# Adafruit_PAM8302.net
KiCad netlist of a schematic drawn in EAGLE
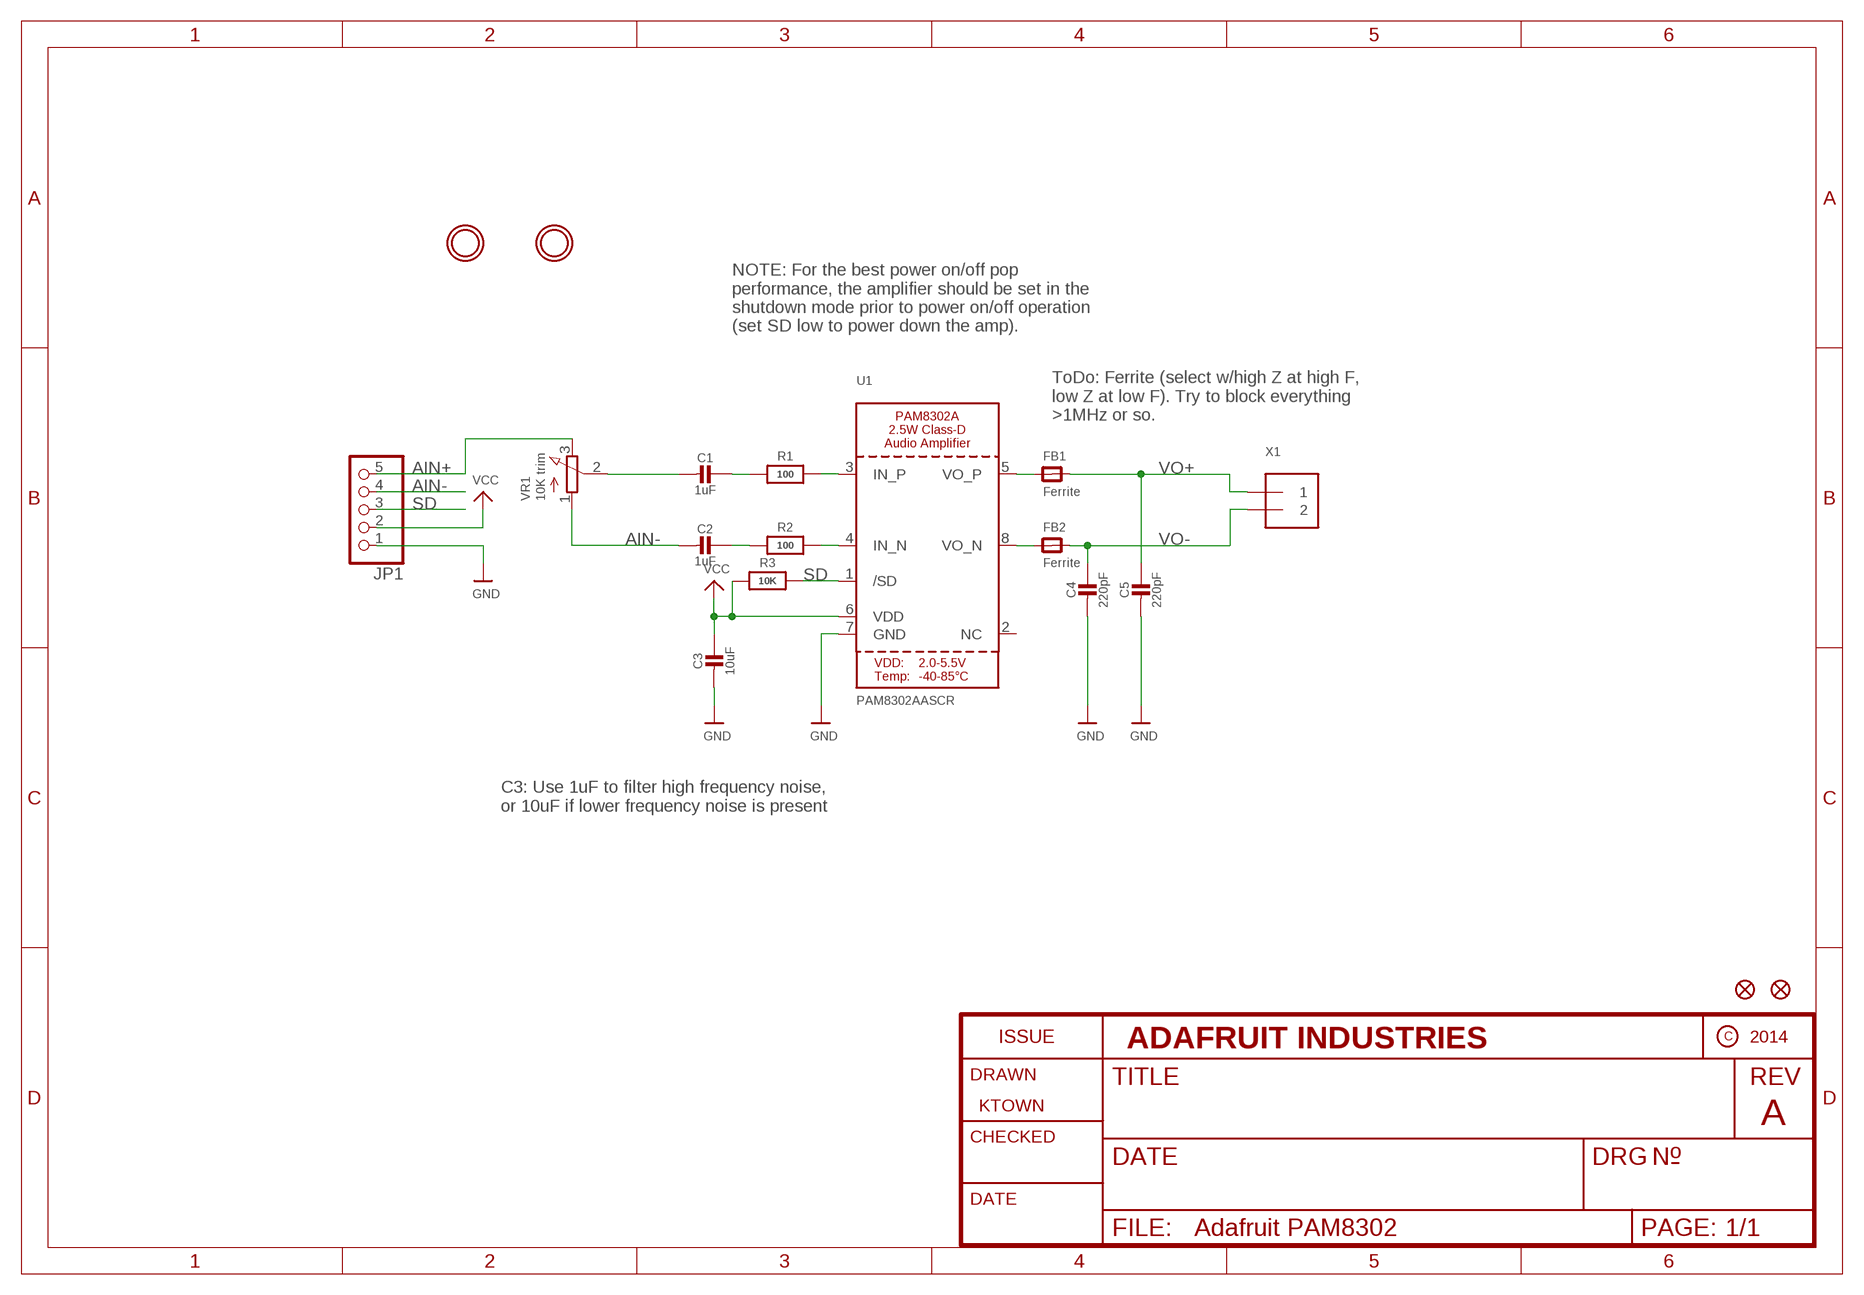
[diagram p0: schematic, sheet 1]

(export (version "E")
  (design (tool "Eeschema 10.0.6"))
  (components
    (comp (ref "C1")
      (value "1uF")
      (footprint "eagle-import:0805-NO")
      (libsource (lib "eagle-import") (part "CAP_CERAMIC0805-NOOUTLINE"))
    )
    (comp (ref "C2")
      (value "1uF")
      (footprint "eagle-import:0805-NO")
      (libsource (lib "eagle-import") (part "CAP_CERAMIC0805-NOOUTLINE"))
    )
    (comp (ref "C3")
      (value "10uF")
      (footprint "eagle-import:0805-NO")
      (libsource (lib "eagle-import") (part "CAP_CERAMIC0805-NOOUTLINE"))
    )
    (comp (ref "C4")
      (value "220pF")
      (footprint "eagle-import:0805-NO")
      (libsource (lib "eagle-import") (part "CAP_CERAMIC0805-NOOUTLINE"))
    )
    (comp (ref "C5")
      (value "220pF")
      (footprint "eagle-import:0805-NO")
      (libsource (lib "eagle-import") (part "CAP_CERAMIC0805-NOOUTLINE"))
    )
    (comp (ref "FB1")
      (value "Ferrite")
      (footprint "eagle-import:_0805")
      (libsource (lib "eagle-import") (part "FERRITE_0805"))
    )
    (comp (ref "FB2")
      (value "Ferrite")
      (footprint "eagle-import:_0805")
      (libsource (lib "eagle-import") (part "FERRITE_0805"))
    )
    (comp (ref "FID1")
      (value "FIDUCIAL\"\"")
      (footprint "eagle-import:FIDUCIAL_1MM")
      (libsource (lib "eagle-import") (part "FIDUCIAL{dblquote}{dblquote}"))
    )
    (comp (ref "FID2")
      (value "FIDUCIAL\"\"")
      (footprint "eagle-import:FIDUCIAL_1MM")
      (libsource (lib "eagle-import") (part "FIDUCIAL{dblquote}{dblquote}"))
    )
    (comp (ref "JP1")
      (value "HEADER-1X570MIL")
      (footprint "eagle-import:1X05_ROUND_70")
      (libsource (lib "eagle-import") (part "HEADER-1X570MIL"))
    )
    (comp (ref "R1")
      (value "100")
      (footprint "eagle-import:0805-NO")
      (libsource (lib "eagle-import") (part "RESISTOR0805_NOOUTLINE"))
    )
    (comp (ref "R2")
      (value "100")
      (footprint "eagle-import:0805-NO")
      (libsource (lib "eagle-import") (part "RESISTOR0805_NOOUTLINE"))
    )
    (comp (ref "R3")
      (value "10K")
      (footprint "eagle-import:0805-NO")
      (libsource (lib "eagle-import") (part "RESISTOR0805_NOOUTLINE"))
    )
    (comp (ref "U$10")
      (value "MOUNTINGHOLE2.0")
      (footprint "eagle-import:MOUNTINGHOLE_2.0_PLATED")
      (libsource (lib "eagle-import") (part "MOUNTINGHOLE2.0"))
    )
    (comp (ref "U$11")
      (value "MOUNTINGHOLE2.0")
      (footprint "eagle-import:MOUNTINGHOLE_2.0_PLATED")
      (libsource (lib "eagle-import") (part "MOUNTINGHOLE2.0"))
    )
    (comp (ref "U1")
      (value "PAM8302AASCR")
      (footprint "eagle-import:MSOP8_0.65MM")
      (libsource (lib "eagle-import") (part "AUDIOAMP_PAM8302A"))
    )
    (comp (ref "VR1")
      (value "10K trim")
      (footprint "eagle-import:TRIMPOT_BOURNS_3303W")
      (libsource (lib "eagle-import") (part "TRIMPOT3303W/X"))
    )
    (comp (ref "X1")
      (value "TERMBLOCK_1X2")
      (footprint "eagle-import:TERMBLOCK_1X2-3.5MM")
      (libsource (lib "eagle-import") (part "TERMBLOCK_1X2"))
    )
  )
  (nets
    (net (code "1") (name "/AIN+") (class "Default")
      (node (ref "JP1") (pin "5") (pinfunction "5_5") (pintype "passive"))
      (node (ref "VR1") (pin "3") (pinfunction "E_3") (pintype "passive"))
    )
    (net (code "2") (name "/AIN-") (class "Default")
      (node (ref "C2") (pin "2") (pinfunction "2_2") (pintype "passive"))
      (node (ref "JP1") (pin "4") (pinfunction "4_4") (pintype "passive"))
      (node (ref "VR1") (pin "1") (pinfunction "A_1") (pintype "passive"))
    )
    (net (code "3") (name "/SD") (class "Default")
      (node (ref "JP1") (pin "3") (pinfunction "3_3") (pintype "passive"))
      (node (ref "R3") (pin "2") (pinfunction "2_2") (pintype "passive"))
      (node (ref "U1") (pin "1") (pinfunction "/SD_1") (pintype "input"))
    )
    (net (code "4") (name "/VO+") (class "Default")
      (node (ref "C5") (pin "1") (pinfunction "1_1") (pintype "passive"))
      (node (ref "FB1") (pin "2") (pinfunction "P$2_2") (pintype "passive"))
      (node (ref "X1") (pin "1") (pinfunction "1_1") (pintype "passive"))
    )
    (net (code "5") (name "/VO-") (class "Default")
      (node (ref "C4") (pin "1") (pinfunction "1_1") (pintype "passive"))
      (node (ref "FB2") (pin "2") (pinfunction "P$2_2") (pintype "passive"))
      (node (ref "X1") (pin "2") (pinfunction "2_2") (pintype "passive"))
    )
    (net (code "6") (name "GND") (class "Default")
      (node (ref "C3") (pin "2") (pinfunction "2_2") (pintype "passive"))
      (node (ref "C4") (pin "2") (pinfunction "2_2") (pintype "passive"))
      (node (ref "C5") (pin "2") (pinfunction "2_2") (pintype "passive"))
      (node (ref "JP1") (pin "1") (pinfunction "1_1") (pintype "passive"))
      (node (ref "U1") (pin "7") (pinfunction "GND_7") (pintype "power_in"))
    )
    (net (code "7") (name "Net-(C1-Pad1)") (class "Default")
      (node (ref "C1") (pin "1") (pinfunction "1_1") (pintype "passive"))
      (node (ref "R1") (pin "1") (pinfunction "1_1") (pintype "passive"))
    )
    (net (code "8") (name "Net-(C2-Pad1)") (class "Default")
      (node (ref "C2") (pin "1") (pinfunction "1_1") (pintype "passive"))
      (node (ref "R2") (pin "1") (pinfunction "1_1") (pintype "passive"))
    )
    (net (code "9") (name "Net-(FB1-P$1)") (class "Default")
      (node (ref "FB1") (pin "1") (pinfunction "P$1_1") (pintype "passive"))
      (node (ref "U1") (pin "5") (pinfunction "VO_P_5") (pintype "output"))
    )
    (net (code "10") (name "Net-(FB2-P$1)") (class "Default")
      (node (ref "FB2") (pin "1") (pinfunction "P$1_1") (pintype "passive"))
      (node (ref "U1") (pin "8") (pinfunction "VO_N_8") (pintype "output"))
    )
    (net (code "11") (name "Net-(U1-IN_N)") (class "Default")
      (node (ref "R2") (pin "2") (pinfunction "2_2") (pintype "passive"))
      (node (ref "U1") (pin "4") (pinfunction "IN_N_4") (pintype "input"))
    )
    (net (code "12") (name "Net-(U1-IN_P)") (class "Default")
      (node (ref "R1") (pin "2") (pinfunction "2_2") (pintype "passive"))
      (node (ref "U1") (pin "3") (pinfunction "IN_P_3") (pintype "input"))
    )
    (net (code "13") (name "Net-(VR1-S)") (class "Default")
      (node (ref "C1") (pin "2") (pinfunction "2_2") (pintype "passive"))
      (node (ref "VR1") (pin "2") (pinfunction "S_2") (pintype "passive"))
    )
    (net (code "14") (name "VCC") (class "Default")
      (node (ref "C3") (pin "1") (pinfunction "1_1") (pintype "passive"))
      (node (ref "JP1") (pin "2") (pinfunction "2_2") (pintype "passive"))
      (node (ref "R3") (pin "1") (pinfunction "1_1") (pintype "passive"))
      (node (ref "U1") (pin "6") (pinfunction "VDD_6") (pintype "power_in"))
    )
    (net (code "15") (name "unconnected-(U1-NC-Pad2)") (class "Default")
      (node (ref "U1") (pin "2") (pinfunction "NC_2") (pintype "no_connect"))
    )
  )
)
